# Power.net
KiCad netlist of a schematic drawn in Altium Designer
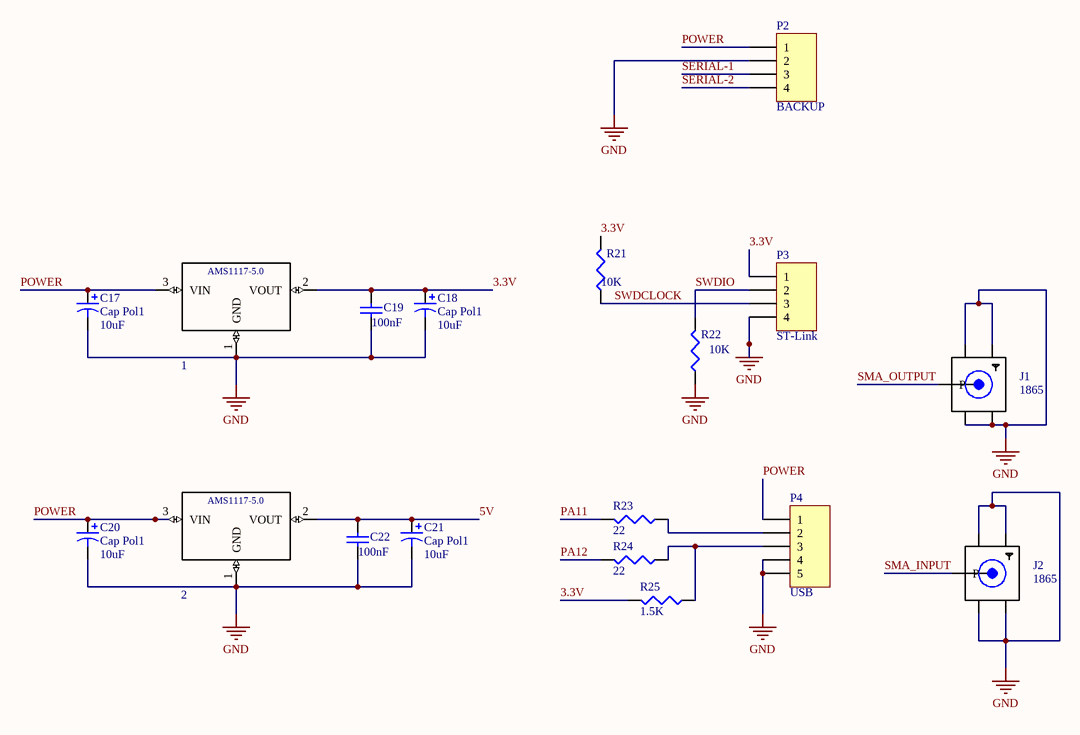
[diagram p0: Power.SchDoc]

(export (version "E")
  (design (tool "Eeschema 10.0.6"))
  (components
    (comp (ref "1")
      (value "AMS1117-3.3")
      (footprint "SOT223")
      (description "Sot-223")
      (fields (field (name "MP") "AMS1117-5.0") (field (name "MF") "ams"))
      (libsource (lib "AMS1117-5.0") (part "AMS1117-5.0"))
    )
    (comp (ref "2")
      (value "AMS1117-5.0")
      (footprint "SOT223")
      (description "Sot-223")
      (fields (field (name "MF") "ams"))
      (libsource (lib "AMS1117-5.0") (part "AMS1117-5.0"))
    )
    (comp (ref "C17")
      (value "Cap Pol1")
      (footprint "RAD-0.2")
      (description "Polarized Capacitor (Radial)")
      (fields (field (name "ALTIUM_VALUE") "10uF") (field (name "PUBLISHER") "Altium Limited"))
      (libsource (lib "Miscellaneous Devices") (part "Cap Pol1"))
    )
    (comp (ref "C18")
      (value "Cap Pol1")
      (footprint "RAD-0.2")
      (description "Polarized Capacitor (Radial)")
      (fields (field (name "ALTIUM_VALUE") "10uF") (field (name "PUBLISHER") "Altium Limited"))
      (libsource (lib "Miscellaneous Devices") (part "Cap Pol1"))
    )
    (comp (ref "C19")
      (value "100nF")
      (footprint "1608[0603]")
      (description "Capacitor (Semiconductor SIM Model)")
      (fields (field (name "Comment") "Cap Semi") (field (name "PUBLISHER") "Altium Limited"))
      (libsource (lib "Miscellaneous Devices") (part "Cap Semi"))
    )
    (comp (ref "C20")
      (value "Cap Pol1")
      (footprint "RAD-0.2")
      (description "Polarized Capacitor (Radial)")
      (fields (field (name "ALTIUM_VALUE") "10uF") (field (name "PUBLISHER") "Altium Limited"))
      (libsource (lib "Miscellaneous Devices") (part "Cap Pol1"))
    )
    (comp (ref "C21")
      (value "Cap Pol1")
      (footprint "RAD-0.2")
      (description "Polarized Capacitor (Radial)")
      (fields (field (name "ALTIUM_VALUE") "10uF") (field (name "PUBLISHER") "Altium Limited"))
      (libsource (lib "Miscellaneous Devices") (part "Cap Pol1"))
    )
    (comp (ref "C22")
      (value "100nF")
      (footprint "1608[0603]")
      (description "Capacitor (Semiconductor SIM Model)")
      (fields (field (name "Comment") "Cap Semi") (field (name "PUBLISHER") "Altium Limited"))
      (libsource (lib "Miscellaneous Devices") (part "Cap Semi"))
    )
    (comp (ref "J1")
      (value "1865")
      (footprint "ADAFRUIT_1865_1865(Primary)")
      (description "ROUND STANDOFF 4-40 BRASS 5/8")
      (fields (field (name "MF") "Keystone"))
      (libsource (lib "1865") (part "1865"))
    )
    (comp (ref "J2")
      (value "1865")
      (footprint "ADAFRUIT_1865_1865(Primary)")
      (description "ROUND STANDOFF 4-40 BRASS 5/8")
      (fields (field (name "MF") "Keystone"))
      (libsource (lib "1865") (part "1865"))
    )
    (comp (ref "P2")
      (value "BACKUP")
      (footprint "MOLEX KK 0022272041")
      (description "Header, 4-Pin")
      (fields (field (name "PUBLISHER") "Altium Limited"))
      (libsource (lib "Miscellaneous Connectors") (part "Header 4"))
    )
    (comp (ref "P3")
      (value "ST-Link")
      (footprint "MOLEX KK 0022272041")
      (description "Header, 4-Pin")
      (fields (field (name "PUBLISHER") "Altium Limited"))
      (libsource (lib "Miscellaneous Connectors") (part "Header 4"))
    )
    (comp (ref "P4")
      (value "USB")
      (footprint "FCI USB 10033526-N3212LF")
      (description "Header, 5-Pin")
      (fields (field (name "PUBLISHER") "Altium Limited"))
      (libsource (lib "Miscellaneous Connectors") (part "Header 5"))
    )
    (comp (ref "R21")
      (value "10K")
      (footprint "J1-0603")
      (description "Resistor")
      (fields (field (name "Comment") "Res3") (field (name "PUBLISHER") "Altium Limited"))
      (libsource (lib "Miscellaneous Devices") (part "Res3"))
    )
    (comp (ref "R22")
      (value "10K")
      (footprint "J1-0603")
      (description "Resistor")
      (fields (field (name "Comment") "Res3") (field (name "PUBLISHER") "Altium Limited"))
      (libsource (lib "Miscellaneous Devices") (part "Res3"))
    )
    (comp (ref "R23")
      (value "22")
      (footprint "J1-0603")
      (description "Resistor")
      (fields (field (name "Comment") "Res3") (field (name "PUBLISHER") "Altium Limited"))
      (libsource (lib "Miscellaneous Devices") (part "Res3"))
    )
    (comp (ref "R24")
      (value "22")
      (footprint "J1-0603")
      (description "Resistor")
      (fields (field (name "Comment") "Res3") (field (name "PUBLISHER") "Altium Limited"))
      (libsource (lib "Miscellaneous Devices") (part "Res3"))
    )
    (comp (ref "R25")
      (value "1.5K")
      (footprint "J1-0603")
      (description "Resistor")
      (fields (field (name "Comment") "Res3") (field (name "PUBLISHER") "Altium Limited"))
      (libsource (lib "Miscellaneous Devices") (part "Res3"))
    )
  )
  (nets
    (net (code "1") (name "/3.3V") (class "Default")
      (node (ref "1") (pin "2") (pinfunction "VOUT_2") (pintype "bidirectional"))
      (node (ref "C18") (pin "1") (pinfunction "1_1") (pintype "passive"))
      (node (ref "C19") (pin "2") (pinfunction "2_2") (pintype "passive"))
      (node (ref "P3") (pin "1") (pinfunction "1_1") (pintype "passive"))
      (node (ref "R21") (pin "2") (pinfunction "2_2") (pintype "passive"))
      (node (ref "R25") (pin "2") (pinfunction "2_2") (pintype "passive"))
    )
    (net (code "2") (name "/5V") (class "Default")
      (node (ref "2") (pin "2") (pinfunction "VOUT_2") (pintype "bidirectional"))
      (node (ref "C21") (pin "1") (pinfunction "1_1") (pintype "passive"))
      (node (ref "C22") (pin "2") (pinfunction "2_2") (pintype "passive"))
    )
    (net (code "3") (name "/PA11") (class "Default")
      (node (ref "R23") (pin "2") (pinfunction "2_2") (pintype "passive"))
    )
    (net (code "4") (name "/PA12") (class "Default")
      (node (ref "R24") (pin "2") (pinfunction "2_2") (pintype "passive"))
    )
    (net (code "5") (name "/POWER") (class "Default")
      (node (ref "1") (pin "3") (pinfunction "VIN_3") (pintype "bidirectional"))
      (node (ref "2") (pin "3") (pinfunction "VIN_3") (pintype "bidirectional"))
      (node (ref "C17") (pin "1") (pinfunction "1_1") (pintype "passive"))
      (node (ref "C20") (pin "1") (pinfunction "1_1") (pintype "passive"))
      (node (ref "P2") (pin "1") (pinfunction "1_1") (pintype "passive"))
      (node (ref "P4") (pin "1") (pinfunction "1_1") (pintype "passive"))
    )
    (net (code "6") (name "/SERIAL-1") (class "Default")
      (node (ref "P2") (pin "3") (pinfunction "3_3") (pintype "passive"))
    )
    (net (code "7") (name "/SERIAL-2") (class "Default")
      (node (ref "P2") (pin "4") (pinfunction "4_4") (pintype "passive"))
    )
    (net (code "8") (name "/SMA_INPUT") (class "Default")
      (node (ref "J2") (pin "P") (pinfunction "P_P") (pintype "bidirectional"))
    )
    (net (code "9") (name "/SMA_OUTPUT") (class "Default")
      (node (ref "J1") (pin "P") (pinfunction "P_P") (pintype "bidirectional"))
    )
    (net (code "10") (name "/SWDCLOCK") (class "Default")
      (node (ref "P3") (pin "3") (pinfunction "3_3") (pintype "passive"))
      (node (ref "R21") (pin "1") (pinfunction "1_1") (pintype "passive"))
    )
    (net (code "11") (name "/SWDIO") (class "Default")
      (node (ref "P3") (pin "2") (pinfunction "2_2") (pintype "passive"))
      (node (ref "R22") (pin "2") (pinfunction "2_2") (pintype "passive"))
    )
    (net (code "12") (name "GND") (class "Default")
      (node (ref "1") (pin "1") (pinfunction "GND_1") (pintype "bidirectional"))
      (node (ref "2") (pin "1") (pinfunction "GND_1") (pintype "bidirectional"))
      (node (ref "C17") (pin "2") (pinfunction "2_2") (pintype "passive"))
      (node (ref "C18") (pin "2") (pinfunction "2_2") (pintype "passive"))
      (node (ref "C19") (pin "1") (pinfunction "1_1") (pintype "passive"))
      (node (ref "C20") (pin "2") (pinfunction "2_2") (pintype "passive"))
      (node (ref "C21") (pin "2") (pinfunction "2_2") (pintype "passive"))
      (node (ref "C22") (pin "1") (pinfunction "1_1") (pintype "passive"))
      (node (ref "J1") (pin "GND1") (pinfunction "GND1_GND1") (pintype "power_in"))
      (node (ref "J1") (pin "GND2") (pinfunction "GND2_GND2") (pintype "power_in"))
      (node (ref "J1") (pin "GND3") (pinfunction "GND3_GND3") (pintype "power_in"))
      (node (ref "J1") (pin "GND4") (pinfunction "GND4_GND4") (pintype "power_in"))
      (node (ref "J2") (pin "GND1") (pinfunction "GND1_GND1") (pintype "power_in"))
      (node (ref "J2") (pin "GND2") (pinfunction "GND2_GND2") (pintype "power_in"))
      (node (ref "J2") (pin "GND3") (pinfunction "GND3_GND3") (pintype "power_in"))
      (node (ref "J2") (pin "GND4") (pinfunction "GND4_GND4") (pintype "power_in"))
      (node (ref "P2") (pin "2") (pinfunction "2_2") (pintype "passive"))
      (node (ref "P3") (pin "4") (pinfunction "4_4") (pintype "passive"))
      (node (ref "P4") (pin "4") (pinfunction "4_4") (pintype "passive"))
      (node (ref "P4") (pin "5") (pinfunction "5_5") (pintype "passive"))
      (node (ref "R22") (pin "1") (pinfunction "1_1") (pintype "passive"))
    )
    (net (code "13") (name "Net-(P4-Pad2)") (class "Default")
      (node (ref "P4") (pin "2") (pinfunction "2_2") (pintype "passive"))
      (node (ref "R23") (pin "1") (pinfunction "1_1") (pintype "passive"))
    )
    (net (code "14") (name "Net-(P4-Pad3)") (class "Default")
      (node (ref "P4") (pin "3") (pinfunction "3_3") (pintype "passive"))
      (node (ref "R24") (pin "1") (pinfunction "1_1") (pintype "passive"))
      (node (ref "R25") (pin "1") (pinfunction "1_1") (pintype "passive"))
    )
  )
)
